# s2_sch.net
KiCad netlist of a schematic drawn in EasyEDA
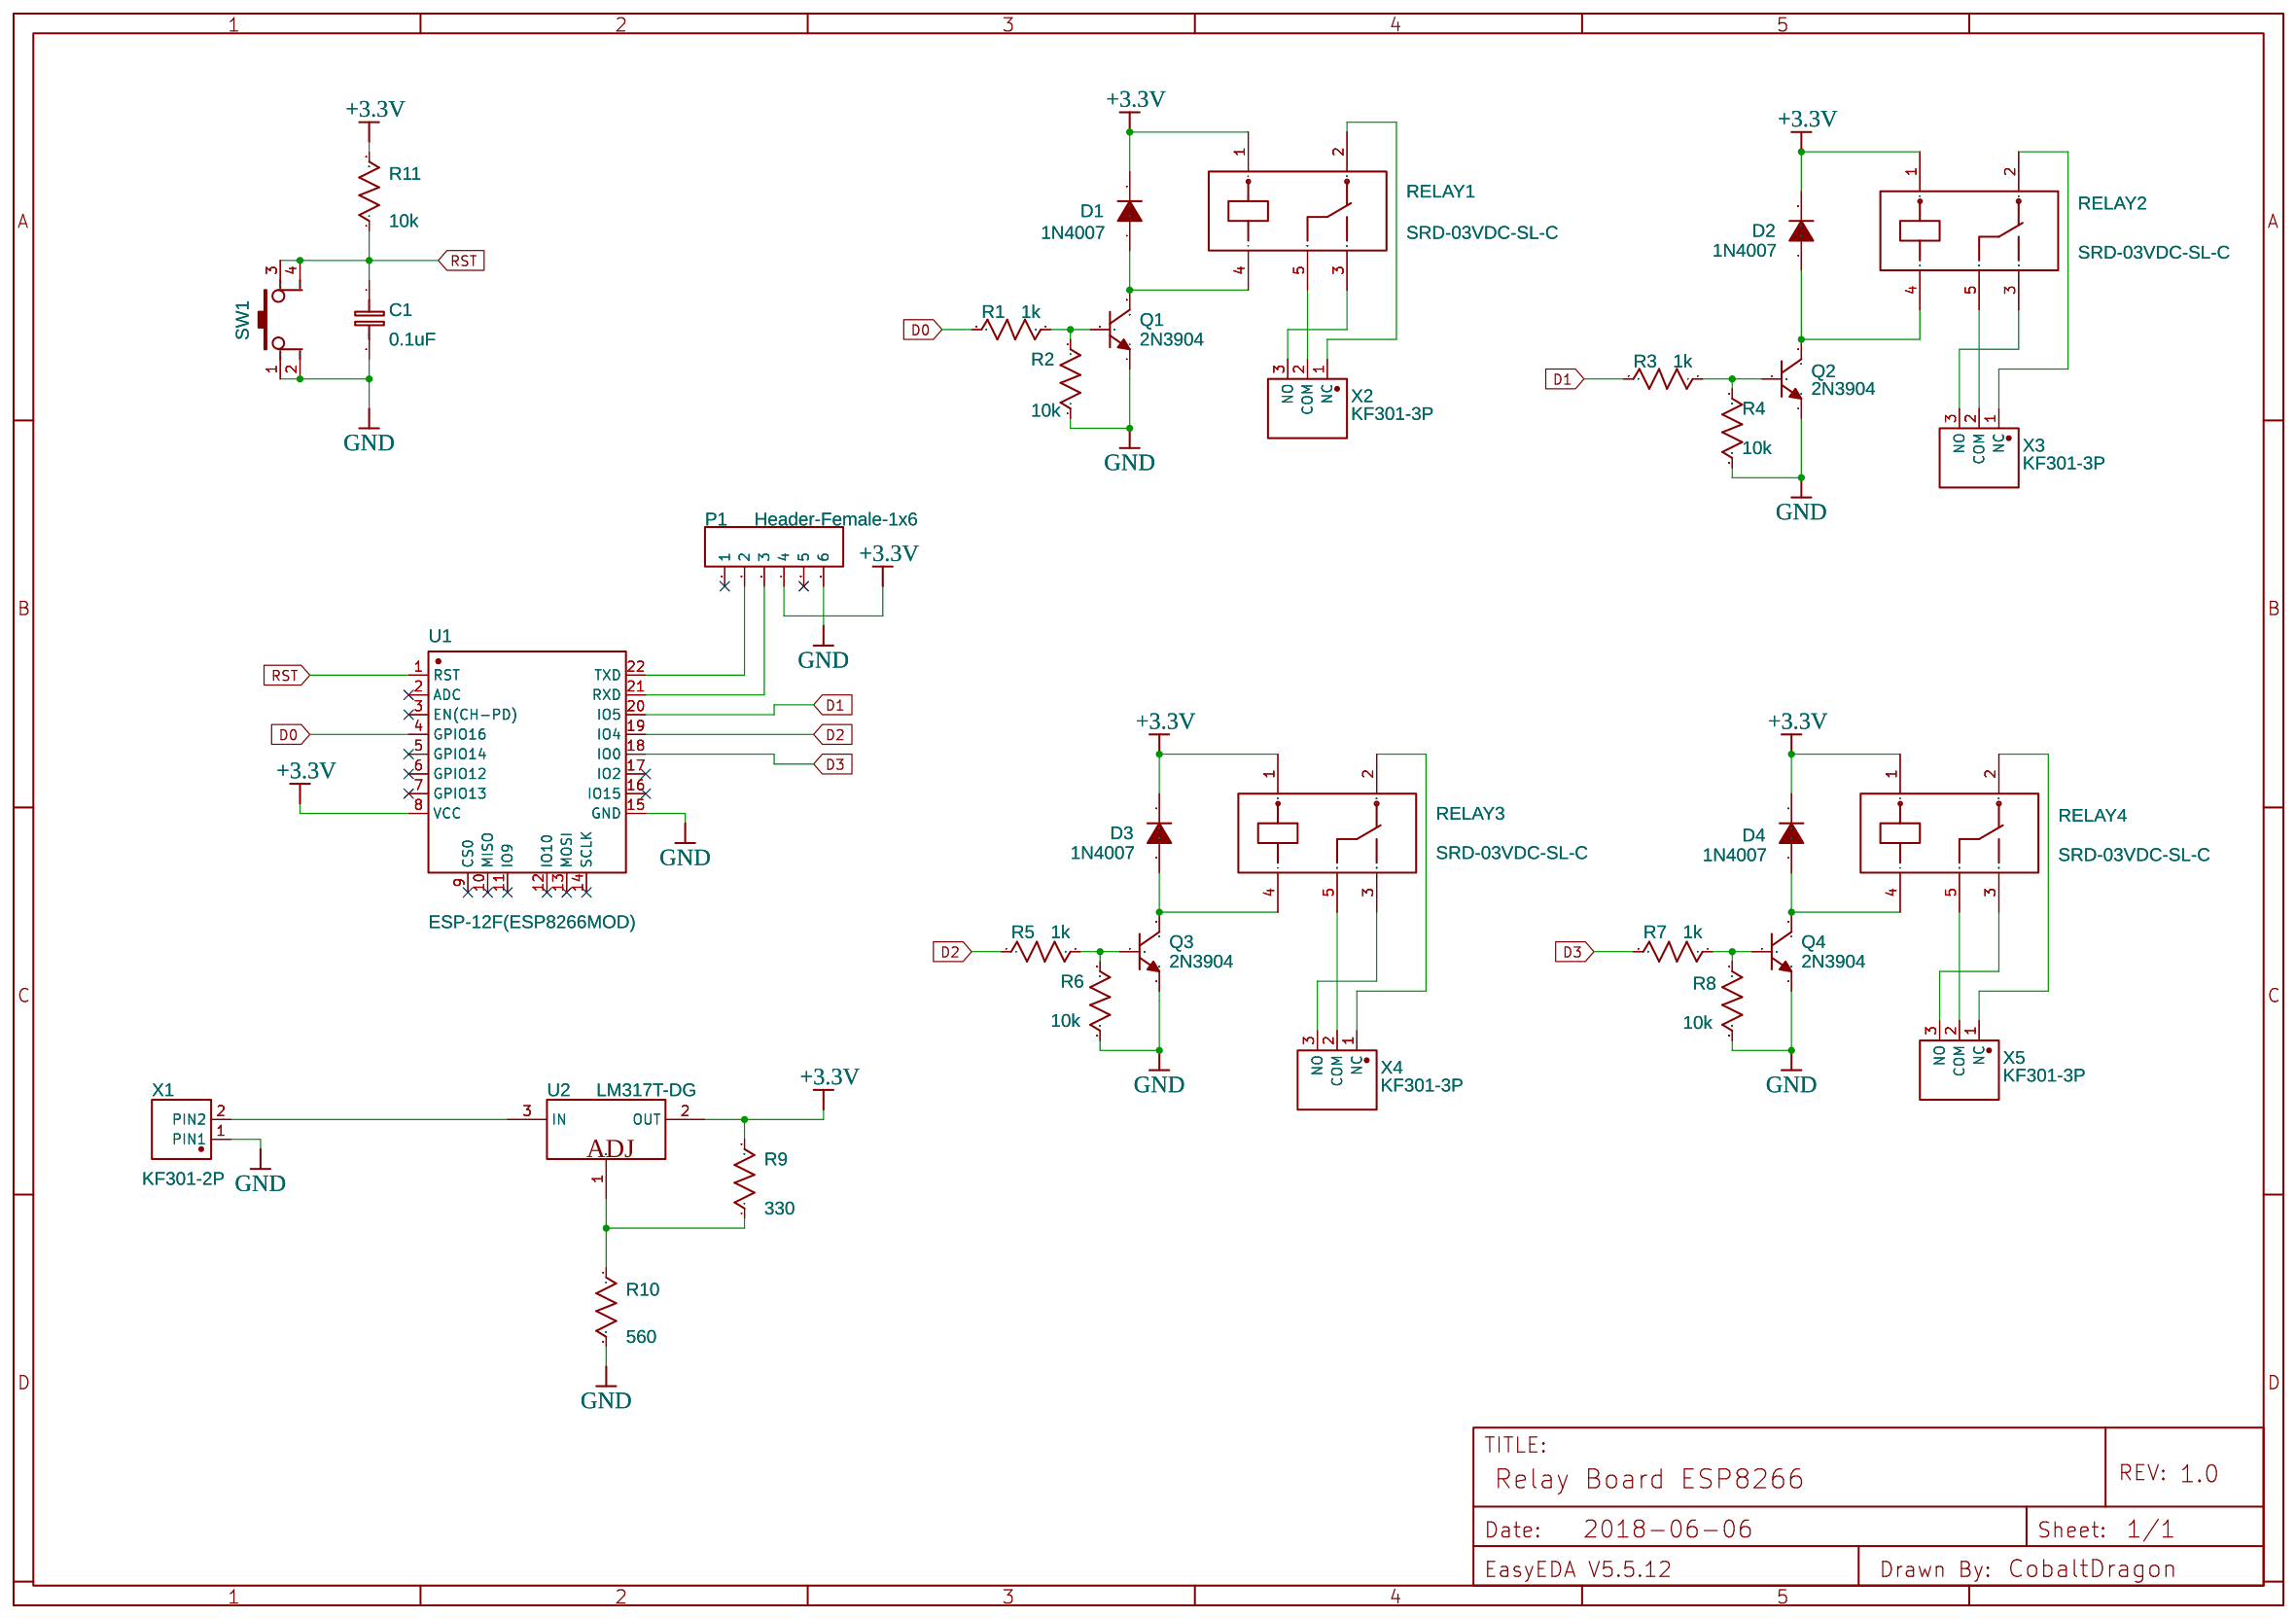
[diagram p0: schematic sheet]

(export (version "E")
  (design (tool "Eeschema 10.0.6"))
  (components
    (comp (ref "C1")
      (value "0.1uF")
      (fields (field (name "BOM_Manufacturer Part") "?"))
      (libsource (lib "") (part "Capacitor"))
    )
    (comp (ref "D1")
      (value "1N4007")
      (fields (field (name "BOM_Supplier Part") "C78540"))
      (libsource (lib "") (part "Unknown_565_100"))
    )
    (comp (ref "D2")
      (value "1N4007")
      (fields (field (name "BOM_Supplier Part") "C78540"))
      (libsource (lib "") (part "Unknown_905_110"))
    )
    (comp (ref "D3")
      (value "1N4007")
      (fields (field (name "BOM_Supplier Part") "C78540"))
      (libsource (lib "") (part "Unknown_580_415"))
    )
    (comp (ref "D4")
      (value "1N4007")
      (fields (field (name "BOM_Supplier Part") "C78540"))
      (libsource (lib "") (part "Unknown_900_415"))
    )
    (comp (ref "P1")
      (value "Header-Female-1x6")
      (fields
        (field (name "BOM_Manufacturer Part") "Female header 1*6p")
        (field (name "BOM_Supplier Part") "C40877")
      )
      (libsource (lib "") (part "Unknown_385_275"))
    )
    (comp (ref "Q1")
      (value "2N3904")
      (fields (field (name "BOM_Supplier Part") "C118538"))
      (libsource (lib "") (part "Unknown_555_160"))
    )
    (comp (ref "Q2")
      (value "2N3904")
      (fields (field (name "BOM_Supplier Part") "C118538"))
      (libsource (lib "") (part "Unknown_895_185"))
    )
    (comp (ref "Q3")
      (value "2N3904")
      (fields (field (name "BOM_Supplier Part") "C118538"))
      (libsource (lib "") (part "Unknown_570_475"))
    )
    (comp (ref "Q4")
      (value "2N3904")
      (fields (field (name "BOM_Supplier Part") "C118538"))
      (libsource (lib "") (part "Unknown_890_475"))
    )
    (comp (ref "R1")
      (value "1k")
      (fields (field (name "BOM_Manufacturer Part") "?"))
      (libsource (lib "") (part "Res_AXIAL-0.3(1/8W)_US"))
    )
    (comp (ref "R2")
      (value "10k")
      (fields (field (name "BOM_Manufacturer Part") "?"))
      (libsource (lib "") (part "Res_AXIAL-0.3(1/8W)_US_1"))
    )
    (comp (ref "R3")
      (value "1k")
      (fields (field (name "BOM_Manufacturer Part") "?"))
      (libsource (lib "") (part "Res_AXIAL-0.3(1/8W)_US_3"))
    )
    (comp (ref "R4")
      (value "10k")
      (fields (field (name "BOM_Manufacturer Part") "?"))
      (libsource (lib "") (part "Res_AXIAL-0.3(1/8W)_US_2"))
    )
    (comp (ref "R5")
      (value "1k")
      (fields (field (name "BOM_Manufacturer Part") "?"))
      (libsource (lib "") (part "Res_AXIAL-0.3(1/8W)_US"))
    )
    (comp (ref "R6")
      (value "10k")
      (fields (field (name "BOM_Manufacturer Part") "?"))
      (libsource (lib "") (part "Res_AXIAL-0.3(1/8W)_US_1"))
    )
    (comp (ref "R7")
      (value "1k")
      (fields (field (name "BOM_Manufacturer Part") "?"))
      (libsource (lib "") (part "Res_AXIAL-0.3(1/8W)_US_3"))
    )
    (comp (ref "R8")
      (value "10k")
      (fields (field (name "BOM_Manufacturer Part") "?"))
      (libsource (lib "") (part "Res_AXIAL-0.3(1/8W)_US_2"))
    )
    (comp (ref "R9")
      (value "330")
      (fields (field (name "BOM_Manufacturer Part") "?"))
      (libsource (lib "") (part "Res_AXIAL-0.3(1/8W)_US_1"))
    )
    (comp (ref "R10")
      (value "560")
      (fields (field (name "BOM_Manufacturer Part") "?"))
      (libsource (lib "") (part "Res_AXIAL-0.3(1/8W)_US_2"))
    )
    (comp (ref "R11")
      (value "10k")
      (fields (field (name "BOM_Manufacturer Part") "?"))
      (libsource (lib "") (part "Res_AXIAL-0.3(1/8W)_US_1"))
    )
    (comp (ref "RELAY1")
      (value "SRD-03VDC-SL-C")
      (fields (field (name "BOM_Supplier Part") "C24585"))
      (libsource (lib "") (part "Unknown_655_100"))
    )
    (comp (ref "RELAY2")
      (value "SRD-03VDC-SL-C")
      (fields (field (name "BOM_Supplier Part") "C24585"))
      (libsource (lib "") (part "Unknown_995_110"))
    )
    (comp (ref "RELAY3")
      (value "SRD-03VDC-SL-C")
      (fields (field (name "BOM_Supplier Part") "C24585"))
      (libsource (lib "") (part "Unknown_670_415"))
    )
    (comp (ref "RELAY4")
      (value "SRD-03VDC-SL-C")
      (fields (field (name "BOM_Supplier Part") "C24585"))
      (libsource (lib "") (part "Unknown_985_415"))
    )
    (comp (ref "SW1")
      (value "SWITCH,4.5*4.5*3.8PLASTIC HEAD,260G, 0.25MM,STRAIGHT LINE")
      (fields
        (field (name "BOM_Manufacturer Part") "Switch,4.5*4.5*3.8Plastic head,260G, 0.25mm,Straight line")
        (field (name "BOM_Supplier Part") "C71853")
      )
      (libsource (lib "") (part "Unknown_145_155"))
    )
    (comp (ref "U1")
      (value "ESP-12F(ESP8266MOD)")
      (fields (field (name "BOM_Supplier Part") "C82891"))
      (libsource (lib "") (part "Unknown_260_375"))
    )
    (comp (ref "U2")
      (value "LM317T-DG")
      (fields (field (name "BOM_Supplier Part") "C18718"))
      (libsource (lib "") (part "Unknown_300_560"))
    )
    (comp (ref "X1") (value "KF301-2P") (libsource (lib "") (part "Unknown_100_580")))
    (comp (ref "X2") (value "KF301-3P") (libsource (lib "") (part "Unknown_675_185")))
    (comp (ref "X3") (value "KF301-3P") (libsource (lib "") (part "Unknown_1015_210")))
    (comp (ref "X4") (value "KF301-3P") (libsource (lib "") (part "Unknown_690_525")))
    (comp (ref "X5") (value "KF301-3P") (libsource (lib "") (part "Unknown_1005_520")))
  )
  (nets
    (net (code "1") (name "+3.3V") (class "Default")
      (node (ref "D1") (pin "2") (pinfunction "K_2") (pintype "unspecified"))
      (node (ref "D2") (pin "2") (pinfunction "K_2") (pintype "unspecified"))
      (node (ref "D3") (pin "2") (pinfunction "K_2") (pintype "unspecified"))
      (node (ref "D4") (pin "2") (pinfunction "K_2") (pintype "unspecified"))
      (node (ref "P1") (pin "4") (pinfunction "4_4") (pintype "input"))
      (node (ref "R11") (pin "2") (pinfunction "2_2") (pintype "unspecified"))
      (node (ref "R9") (pin "2") (pinfunction "2_2") (pintype "unspecified"))
      (node (ref "RELAY1") (pin "1") (pinfunction "1_1") (pintype "input"))
      (node (ref "RELAY2") (pin "1") (pinfunction "1_1") (pintype "input"))
      (node (ref "RELAY3") (pin "1") (pinfunction "1_1") (pintype "input"))
      (node (ref "RELAY4") (pin "1") (pinfunction "1_1") (pintype "input"))
      (node (ref "U1") (pin "8") (pinfunction "VCC_8") (pintype "unspecified"))
      (node (ref "U2") (pin "2") (pinfunction "OUT_2") (pintype "passive"))
    )
    (net (code "2") (name "D0") (class "Default")
      (node (ref "R1") (pin "1") (pinfunction "1_1") (pintype "unspecified"))
      (node (ref "U1") (pin "4") (pinfunction "GPIO16_4") (pintype "unspecified"))
    )
    (net (code "3") (name "D1") (class "Default")
      (node (ref "R3") (pin "2") (pinfunction "2_2") (pintype "unspecified"))
      (node (ref "U1") (pin "20") (pinfunction "IO5_20") (pintype "unspecified"))
    )
    (net (code "4") (name "D2") (class "Default")
      (node (ref "R5") (pin "1") (pinfunction "1_1") (pintype "unspecified"))
      (node (ref "U1") (pin "19") (pinfunction "IO4_19") (pintype "unspecified"))
    )
    (net (code "5") (name "D3") (class "Default")
      (node (ref "R7") (pin "2") (pinfunction "2_2") (pintype "unspecified"))
      (node (ref "U1") (pin "18") (pinfunction "IO0_18") (pintype "unspecified"))
    )
    (net (code "6") (name "GND") (class "Default")
      (node (ref "C1") (pin "2") (pinfunction "2_2") (pintype "unspecified"))
      (node (ref "P1") (pin "6") (pinfunction "6_6") (pintype "input"))
      (node (ref "Q1") (pin "1") (pinfunction "E_1") (pintype "unspecified"))
      (node (ref "Q2") (pin "1") (pinfunction "E_1") (pintype "unspecified"))
      (node (ref "Q3") (pin "1") (pinfunction "E_1") (pintype "unspecified"))
      (node (ref "Q4") (pin "1") (pinfunction "E_1") (pintype "unspecified"))
      (node (ref "R10") (pin "2") (pinfunction "2_2") (pintype "unspecified"))
      (node (ref "R2") (pin "1") (pinfunction "1_1") (pintype "unspecified"))
      (node (ref "R4") (pin "2") (pinfunction "2_2") (pintype "unspecified"))
      (node (ref "R6") (pin "1") (pinfunction "1_1") (pintype "unspecified"))
      (node (ref "R8") (pin "2") (pinfunction "2_2") (pintype "unspecified"))
      (node (ref "SW1") (pin "1") (pinfunction "1_1") (pintype "input"))
      (node (ref "SW1") (pin "2") (pinfunction "2_2") (pintype "input"))
      (node (ref "U1") (pin "15") (pinfunction "GND_15") (pintype "unspecified"))
      (node (ref "X1") (pin "1") (pinfunction "PIN1_1") (pintype "unspecified"))
    )
    (net (code "7") (name "Net-(D1-A)") (class "Default")
      (node (ref "D1") (pin "1") (pinfunction "A_1") (pintype "unspecified"))
      (node (ref "Q1") (pin "3") (pinfunction "C_3") (pintype "unspecified"))
      (node (ref "RELAY1") (pin "4") (pinfunction "4_4") (pintype "input"))
    )
    (net (code "8") (name "Net-(D2-A)") (class "Default")
      (node (ref "D2") (pin "1") (pinfunction "A_1") (pintype "unspecified"))
      (node (ref "Q2") (pin "3") (pinfunction "C_3") (pintype "unspecified"))
      (node (ref "RELAY2") (pin "4") (pinfunction "4_4") (pintype "input"))
    )
    (net (code "9") (name "Net-(D3-A)") (class "Default")
      (node (ref "D3") (pin "1") (pinfunction "A_1") (pintype "unspecified"))
      (node (ref "Q3") (pin "3") (pinfunction "C_3") (pintype "unspecified"))
      (node (ref "RELAY3") (pin "4") (pinfunction "4_4") (pintype "input"))
    )
    (net (code "10") (name "Net-(D4-A)") (class "Default")
      (node (ref "D4") (pin "1") (pinfunction "A_1") (pintype "unspecified"))
      (node (ref "Q4") (pin "3") (pinfunction "C_3") (pintype "unspecified"))
      (node (ref "RELAY4") (pin "4") (pinfunction "4_4") (pintype "input"))
    )
    (net (code "11") (name "Net-(Q1-B)") (class "Default")
      (node (ref "Q1") (pin "2") (pinfunction "B_2") (pintype "unspecified"))
      (node (ref "R1") (pin "2") (pinfunction "2_2") (pintype "unspecified"))
      (node (ref "R2") (pin "2") (pinfunction "2_2") (pintype "unspecified"))
    )
    (net (code "12") (name "Net-(Q2-B)") (class "Default")
      (node (ref "Q2") (pin "2") (pinfunction "B_2") (pintype "unspecified"))
      (node (ref "R3") (pin "1") (pinfunction "1_1") (pintype "unspecified"))
      (node (ref "R4") (pin "1") (pinfunction "1_1") (pintype "unspecified"))
    )
    (net (code "13") (name "Net-(Q3-B)") (class "Default")
      (node (ref "Q3") (pin "2") (pinfunction "B_2") (pintype "unspecified"))
      (node (ref "R5") (pin "2") (pinfunction "2_2") (pintype "unspecified"))
      (node (ref "R6") (pin "2") (pinfunction "2_2") (pintype "unspecified"))
    )
    (net (code "14") (name "Net-(Q4-B)") (class "Default")
      (node (ref "Q4") (pin "2") (pinfunction "B_2") (pintype "unspecified"))
      (node (ref "R7") (pin "1") (pinfunction "1_1") (pintype "unspecified"))
      (node (ref "R8") (pin "1") (pinfunction "1_1") (pintype "unspecified"))
    )
    (net (code "15") (name "Net-(U1-RXD)") (class "Default")
      (node (ref "P1") (pin "3") (pinfunction "3_3") (pintype "input"))
      (node (ref "U1") (pin "21") (pinfunction "RXD_21") (pintype "unspecified"))
    )
    (net (code "16") (name "Net-(U1-TXD)") (class "Default")
      (node (ref "P1") (pin "2") (pinfunction "2_2") (pintype "input"))
      (node (ref "U1") (pin "22") (pinfunction "TXD_22") (pintype "unspecified"))
    )
    (net (code "17") (name "Net-(U2-ADJ)") (class "Default")
      (node (ref "R10") (pin "1") (pinfunction "1_1") (pintype "unspecified"))
      (node (ref "R9") (pin "1") (pinfunction "1_1") (pintype "unspecified"))
      (node (ref "U2") (pin "1") (pinfunction "ADJ_1") (pintype "unspecified"))
    )
    (net (code "18") (name "Net-(U2-IN)") (class "Default")
      (node (ref "U2") (pin "3") (pinfunction "IN_3") (pintype "passive"))
      (node (ref "X1") (pin "2") (pinfunction "PIN2_2") (pintype "unspecified"))
    )
    (net (code "19") (name "Net-(X2-COM)") (class "Default")
      (node (ref "RELAY1") (pin "5") (pinfunction "5_5") (pintype "input"))
      (node (ref "X2") (pin "2") (pinfunction "COM_2") (pintype "unspecified"))
    )
    (net (code "20") (name "Net-(X2-NC)") (class "Default")
      (node (ref "RELAY1") (pin "2") (pinfunction "2_2") (pintype "input"))
      (node (ref "X2") (pin "1") (pinfunction "NC_1") (pintype "unspecified"))
    )
    (net (code "21") (name "Net-(X2-NO)") (class "Default")
      (node (ref "RELAY1") (pin "3") (pinfunction "3_3") (pintype "input"))
      (node (ref "X2") (pin "3") (pinfunction "NO_3") (pintype "unspecified"))
    )
    (net (code "22") (name "Net-(X3-COM)") (class "Default")
      (node (ref "RELAY2") (pin "5") (pinfunction "5_5") (pintype "input"))
      (node (ref "X3") (pin "2") (pinfunction "COM_2") (pintype "unspecified"))
    )
    (net (code "23") (name "Net-(X3-NC)") (class "Default")
      (node (ref "RELAY2") (pin "2") (pinfunction "2_2") (pintype "input"))
      (node (ref "X3") (pin "1") (pinfunction "NC_1") (pintype "unspecified"))
    )
    (net (code "24") (name "Net-(X3-NO)") (class "Default")
      (node (ref "RELAY2") (pin "3") (pinfunction "3_3") (pintype "input"))
      (node (ref "X3") (pin "3") (pinfunction "NO_3") (pintype "unspecified"))
    )
    (net (code "25") (name "Net-(X4-COM)") (class "Default")
      (node (ref "RELAY3") (pin "5") (pinfunction "5_5") (pintype "input"))
      (node (ref "X4") (pin "2") (pinfunction "COM_2") (pintype "unspecified"))
    )
    (net (code "26") (name "Net-(X4-NC)") (class "Default")
      (node (ref "RELAY3") (pin "2") (pinfunction "2_2") (pintype "input"))
      (node (ref "X4") (pin "1") (pinfunction "NC_1") (pintype "unspecified"))
    )
    (net (code "27") (name "Net-(X4-NO)") (class "Default")
      (node (ref "RELAY3") (pin "3") (pinfunction "3_3") (pintype "input"))
      (node (ref "X4") (pin "3") (pinfunction "NO_3") (pintype "unspecified"))
    )
    (net (code "28") (name "Net-(X5-COM)") (class "Default")
      (node (ref "RELAY4") (pin "5") (pinfunction "5_5") (pintype "input"))
      (node (ref "X5") (pin "2") (pinfunction "COM_2") (pintype "unspecified"))
    )
    (net (code "29") (name "Net-(X5-NC)") (class "Default")
      (node (ref "RELAY4") (pin "2") (pinfunction "2_2") (pintype "input"))
      (node (ref "X5") (pin "1") (pinfunction "NC_1") (pintype "unspecified"))
    )
    (net (code "30") (name "Net-(X5-NO)") (class "Default")
      (node (ref "RELAY4") (pin "3") (pinfunction "3_3") (pintype "input"))
      (node (ref "X5") (pin "3") (pinfunction "NO_3") (pintype "unspecified"))
    )
    (net (code "31") (name "RST") (class "Default")
      (node (ref "C1") (pin "1") (pinfunction "1_1") (pintype "unspecified"))
      (node (ref "R11") (pin "1") (pinfunction "1_1") (pintype "unspecified"))
      (node (ref "SW1") (pin "3") (pinfunction "3_3") (pintype "input"))
      (node (ref "SW1") (pin "4") (pinfunction "4_4") (pintype "input"))
      (node (ref "U1") (pin "1") (pinfunction "RST_1") (pintype "unspecified"))
    )
    (net (code "32") (name "unconnected-(P1-Pad1)") (class "Default")
      (node (ref "P1") (pin "1") (pinfunction "1_1") (pintype "input+no_connect"))
    )
    (net (code "33") (name "unconnected-(P1-Pad5)") (class "Default")
      (node (ref "P1") (pin "5") (pinfunction "5_5") (pintype "input+no_connect"))
    )
    (net (code "34") (name "unconnected-(U1-ADC-Pad2)") (class "Default")
      (node (ref "U1") (pin "2") (pinfunction "ADC_2") (pintype "unspecified+no_connect"))
    )
    (net (code "35") (name "unconnected-(U1-CS0-Pad9)") (class "Default")
      (node (ref "U1") (pin "9") (pinfunction "CS0_9") (pintype "unspecified+no_connect"))
    )
    (net (code "36") (name "unconnected-(U1-EN(CH-PD)-Pad3)") (class "Default")
      (node (ref "U1") (pin "3") (pinfunction "EN(CH-PD)_3") (pintype "unspecified+no_connect"))
    )
    (net (code "37") (name "unconnected-(U1-GPIO12-Pad6)") (class "Default")
      (node (ref "U1") (pin "6") (pinfunction "GPIO12_6") (pintype "unspecified+no_connect"))
    )
    (net (code "38") (name "unconnected-(U1-GPIO13-Pad7)") (class "Default")
      (node (ref "U1") (pin "7") (pinfunction "GPIO13_7") (pintype "unspecified+no_connect"))
    )
    (net (code "39") (name "unconnected-(U1-GPIO14-Pad5)") (class "Default")
      (node (ref "U1") (pin "5") (pinfunction "GPIO14_5") (pintype "unspecified+no_connect"))
    )
    (net (code "40") (name "unconnected-(U1-IO2-Pad17)") (class "Default")
      (node (ref "U1") (pin "17") (pinfunction "IO2_17") (pintype "unspecified+no_connect"))
    )
    (net (code "41") (name "unconnected-(U1-IO9-Pad11)") (class "Default")
      (node (ref "U1") (pin "11") (pinfunction "IO9_11") (pintype "unspecified+no_connect"))
    )
    (net (code "42") (name "unconnected-(U1-IO10-Pad12)") (class "Default")
      (node (ref "U1") (pin "12") (pinfunction "IO10_12") (pintype "unspecified+no_connect"))
    )
    (net (code "43") (name "unconnected-(U1-IO15-Pad16)") (class "Default")
      (node (ref "U1") (pin "16") (pinfunction "IO15_16") (pintype "unspecified+no_connect"))
    )
    (net (code "44") (name "unconnected-(U1-MISO-Pad10)") (class "Default")
      (node (ref "U1") (pin "10") (pinfunction "MISO_10") (pintype "unspecified+no_connect"))
    )
    (net (code "45") (name "unconnected-(U1-MOSI-Pad13)") (class "Default")
      (node (ref "U1") (pin "13") (pinfunction "MOSI_13") (pintype "unspecified+no_connect"))
    )
    (net (code "46") (name "unconnected-(U1-SCLK-Pad14)") (class "Default")
      (node (ref "U1") (pin "14") (pinfunction "SCLK_14") (pintype "unspecified+no_connect"))
    )
  )
)
